# mcu.net
KiCad netlist of a schematic drawn in Altium Designer
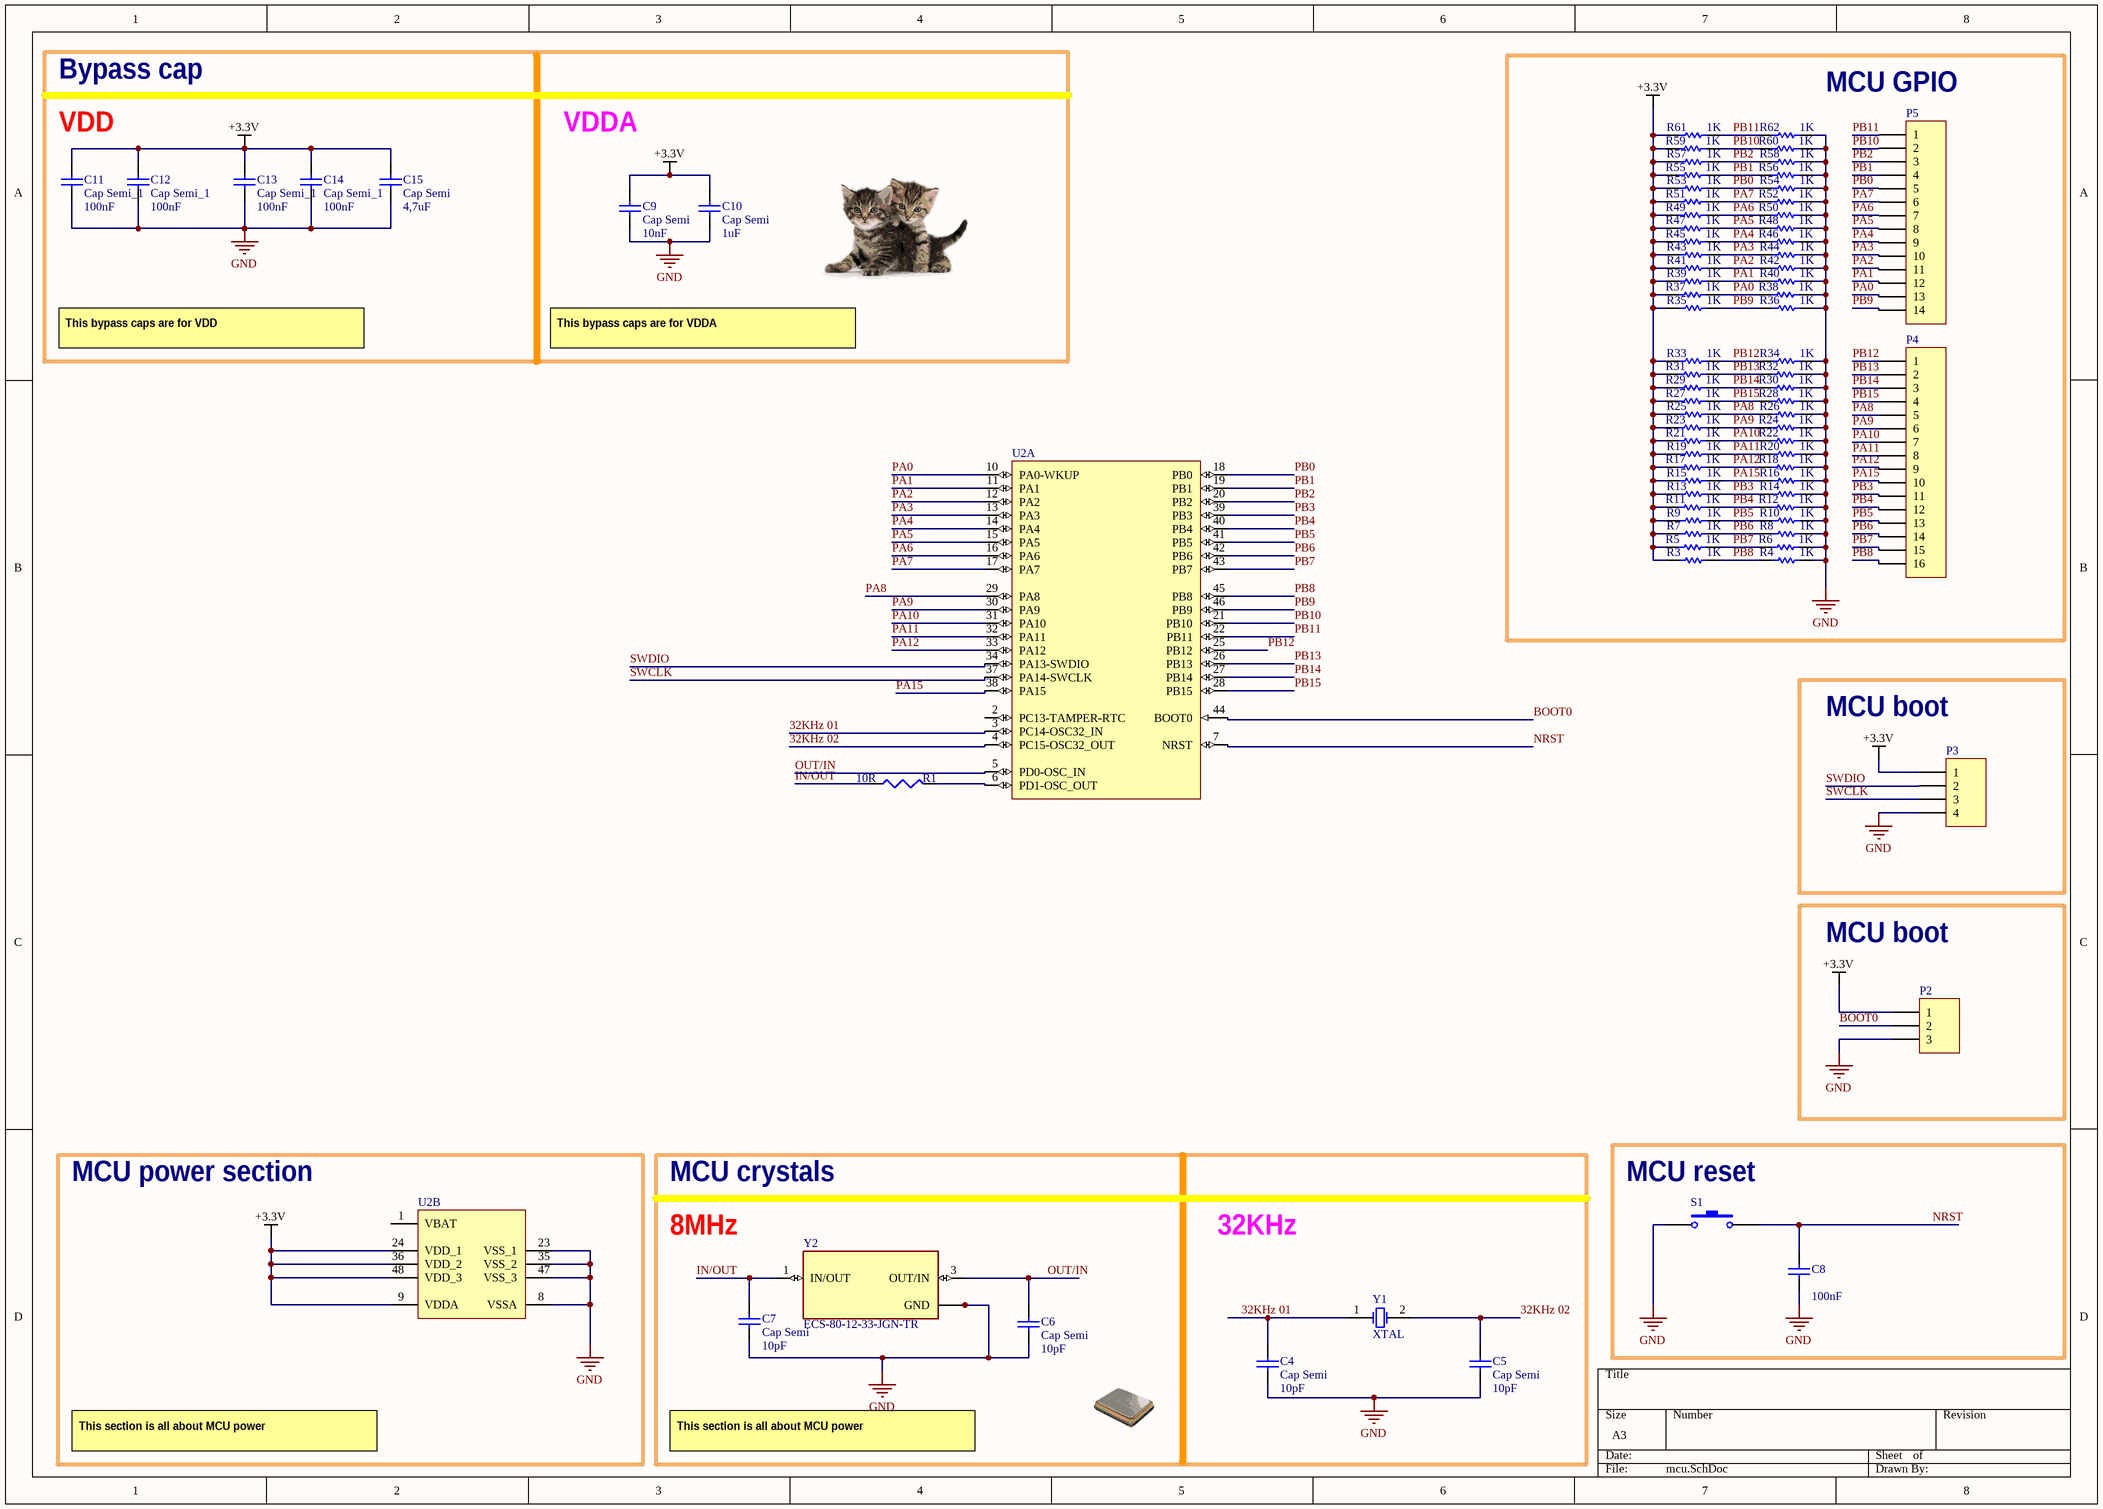
[diagram p0: mcu.SchDoc]

(export (version "E")
  (design (tool "Eeschema 10.0.6"))
  (components
    (comp (ref "C4")
      (value "Cap Semi")
      (footprint "0402")
      (description "Capacitor (Semiconductor SIM Model)")
      (fields (field (name "ALTIUM_VALUE") "10pF") (field (name "PUBLISHER") "Altium Limited"))
      (libsource (lib "Miscellaneous Devices") (part "Cap Semi"))
    )
    (comp (ref "C5")
      (value "Cap Semi")
      (footprint "0402")
      (description "Capacitor (Semiconductor SIM Model)")
      (fields (field (name "ALTIUM_VALUE") "10pF") (field (name "PUBLISHER") "Altium Limited"))
      (libsource (lib "Miscellaneous Devices") (part "Cap Semi"))
    )
    (comp (ref "C6")
      (value "Cap Semi")
      (footprint "0402")
      (description "Capacitor (Semiconductor SIM Model)")
      (fields (field (name "ALTIUM_VALUE") "10pF") (field (name "PUBLISHER") "Altium Limited"))
      (libsource (lib "Miscellaneous Devices") (part "Cap Semi"))
    )
    (comp (ref "C7")
      (value "Cap Semi")
      (footprint "0402")
      (description "Capacitor (Semiconductor SIM Model)")
      (fields (field (name "ALTIUM_VALUE") "10pF") (field (name "PUBLISHER") "Altium Limited"))
      (libsource (lib "Miscellaneous Devices") (part "Cap Semi"))
    )
    (comp (ref "C8")
      (value "100nF")
      (footprint "1608[0603]")
      (description "Capacitor (Semiconductor SIM Model)")
      (fields (field (name "PUBLISHER") "Altium Limited"))
      (libsource (lib "smartmcu") (part "Cap Semi"))
    )
    (comp (ref "C9")
      (value "Cap Semi")
      (footprint "1608[0603]")
      (description "Capacitor (Semiconductor SIM Model)")
      (fields (field (name "ALTIUM_VALUE") "10nF") (field (name "PUBLISHER") "Altium Limited"))
      (libsource (lib "Miscellaneous Devices") (part "Cap Semi"))
    )
    (comp (ref "C10")
      (value "Cap Semi")
      (footprint "1608[0603]")
      (description "Capacitor (Semiconductor SIM Model)")
      (fields (field (name "ALTIUM_VALUE") "1uF") (field (name "PUBLISHER") "Altium Limited"))
      (libsource (lib "Miscellaneous Devices") (part "Cap Semi"))
    )
    (comp (ref "C11")
      (value "Cap Semi_1")
      (footprint "1608[0603]cap")
      (description "Capacitor (Semiconductor SIM Model)")
      (fields (field (name "ALTIUM_VALUE") "100nF") (field (name "PUBLISHER") "Altium Limited"))
      (libsource (lib "smartmcu") (part "Cap Semi_1"))
    )
    (comp (ref "C12")
      (value "Cap Semi_1")
      (footprint "1608[0603]cap")
      (description "Capacitor (Semiconductor SIM Model)")
      (fields (field (name "ALTIUM_VALUE") "100nF") (field (name "PUBLISHER") "Altium Limited"))
      (libsource (lib "smartmcu") (part "Cap Semi_1"))
    )
    (comp (ref "C13")
      (value "Cap Semi_1")
      (footprint "1608[0603]cap")
      (description "Capacitor (Semiconductor SIM Model)")
      (fields (field (name "ALTIUM_VALUE") "100nF") (field (name "PUBLISHER") "Altium Limited"))
      (libsource (lib "smartmcu") (part "Cap Semi_1_2"))
    )
    (comp (ref "C14")
      (value "Cap Semi_1")
      (footprint "1608[0603]cap")
      (description "Capacitor (Semiconductor SIM Model)")
      (fields (field (name "ALTIUM_VALUE") "100nF") (field (name "PUBLISHER") "Altium Limited"))
      (libsource (lib "smartmcu") (part "Cap Semi_1_3"))
    )
    (comp (ref "C15")
      (value "Cap Semi")
      (footprint "1608[0603]cap")
      (description "Capacitor (Semiconductor SIM Model)")
      (fields (field (name "ALTIUM_VALUE") "4,7uF") (field (name "PUBLISHER") "Altium Limited"))
      (libsource (lib "smartmcu") (part "Cap Semi"))
    )
    (comp (ref "P2")
      (value "~")
      (footprint "MHDR1X3body")
      (description "Header, 3-Pin")
      (fields (field (name "PUBLISHER") "Altium Limited"))
      (libsource (lib "smartmcu") (part "MHDR1X3"))
    )
    (comp (ref "P3")
      (value "~")
      (footprint "MHDR1X4body")
      (description "Header, 4-Pin")
      (fields (field (name "PUBLISHER") "Altium Limited"))
      (libsource (lib "smartmcu") (part "MHDR1X4"))
    )
    (comp (ref "P4")
      (value "Header 16")
      (footprint "MY_FE16")
      (description "Header, 16-Pin")
      (fields (field (name "ASID PART NUMBER") "Header 16-AS"))
      (libsource (lib "Mylib+Rev+4") (part "Header 16"))
    )
    (comp (ref "P5")
      (value "Header 14")
      (footprint "MY_FE14")
      (description "Header, 14-Pin")
      (fields (field (name "ASID PART NUMBER") "Header 14-AS"))
      (libsource (lib "Mylib+Rev+4") (part "Header 14"))
    )
    (comp (ref "R1")
      (value "10R")
      (footprint "J1-0603")
      (description "Resistor")
      (fields (field (name "Comment") "Res3") (field (name "PUBLISHER") "Altium Limited"))
      (libsource (lib "Miscellaneous Devices") (part "Res3"))
    )
    (comp (ref "R3")
      (value "1K")
      (footprint "MY_0603")
      (description "Standard resistor")
      (fields (field (name "ASID PART NUMBER") "Res-AS"))
      (libsource (lib "Mylib+Rev+4") (part "Res"))
    )
    (comp (ref "R4")
      (value "1K")
      (footprint "MY_0603")
      (description "Standard resistor")
      (fields (field (name "ASID PART NUMBER") "Res-AS"))
      (libsource (lib "Mylib+Rev+4") (part "Res"))
    )
    (comp (ref "R5")
      (value "1K")
      (footprint "MY_0603")
      (description "Standard resistor")
      (fields (field (name "ASID PART NUMBER") "Res-AS"))
      (libsource (lib "Mylib+Rev+4") (part "Res"))
    )
    (comp (ref "R6")
      (value "1K")
      (footprint "MY_0603")
      (description "Standard resistor")
      (fields (field (name "ASID PART NUMBER") "Res-AS"))
      (libsource (lib "Mylib+Rev+4") (part "Res"))
    )
    (comp (ref "R7")
      (value "1K")
      (footprint "MY_0603")
      (description "Standard resistor")
      (fields (field (name "ASID PART NUMBER") "Res-AS"))
      (libsource (lib "Mylib+Rev+4") (part "Res"))
    )
    (comp (ref "R8")
      (value "1K")
      (footprint "MY_0603")
      (description "Standard resistor")
      (fields (field (name "ASID PART NUMBER") "Res-AS"))
      (libsource (lib "Mylib+Rev+4") (part "Res"))
    )
    (comp (ref "R9")
      (value "1K")
      (footprint "MY_0603")
      (description "Standard resistor")
      (fields (field (name "ASID PART NUMBER") "Res-AS"))
      (libsource (lib "Mylib+Rev+4") (part "Res"))
    )
    (comp (ref "R10")
      (value "1K")
      (footprint "MY_0603")
      (description "Standard resistor")
      (fields (field (name "ASID PART NUMBER") "Res-AS"))
      (libsource (lib "Mylib+Rev+4") (part "Res"))
    )
    (comp (ref "R11")
      (value "1K")
      (footprint "MY_0603")
      (description "Standard resistor")
      (fields (field (name "ASID PART NUMBER") "Res-AS"))
      (libsource (lib "Mylib+Rev+4") (part "Res"))
    )
    (comp (ref "R12")
      (value "1K")
      (footprint "MY_0603")
      (description "Standard resistor")
      (fields (field (name "ASID PART NUMBER") "Res-AS"))
      (libsource (lib "Mylib+Rev+4") (part "Res"))
    )
    (comp (ref "R13")
      (value "1K")
      (footprint "MY_0603")
      (description "Standard resistor")
      (fields (field (name "ASID PART NUMBER") "Res-AS"))
      (libsource (lib "Mylib+Rev+4") (part "Res"))
    )
    (comp (ref "R14")
      (value "1K")
      (footprint "MY_0603")
      (description "Standard resistor")
      (fields (field (name "ASID PART NUMBER") "Res-AS"))
      (libsource (lib "Mylib+Rev+4") (part "Res"))
    )
    (comp (ref "R15")
      (value "1K")
      (footprint "MY_0603")
      (description "Standard resistor")
      (fields (field (name "ASID PART NUMBER") "Res-AS"))
      (libsource (lib "Mylib+Rev+4") (part "Res"))
    )
    (comp (ref "R16")
      (value "1K")
      (footprint "MY_0603")
      (description "Standard resistor")
      (fields (field (name "ASID PART NUMBER") "Res-AS"))
      (libsource (lib "Mylib+Rev+4") (part "Res"))
    )
    (comp (ref "R17")
      (value "1K")
      (footprint "MY_0603")
      (description "Standard resistor")
      (fields (field (name "ASID PART NUMBER") "Res-AS"))
      (libsource (lib "Mylib+Rev+4") (part "Res"))
    )
    (comp (ref "R18")
      (value "1K")
      (footprint "MY_0603")
      (description "Standard resistor")
      (fields (field (name "ASID PART NUMBER") "Res-AS"))
      (libsource (lib "Mylib+Rev+4") (part "Res"))
    )
    (comp (ref "R19")
      (value "1K")
      (footprint "MY_0603")
      (description "Standard resistor")
      (fields (field (name "ASID PART NUMBER") "Res-AS"))
      (libsource (lib "Mylib+Rev+4") (part "Res"))
    )
    (comp (ref "R20")
      (value "1K")
      (footprint "MY_0603")
      (description "Standard resistor")
      (fields (field (name "ASID PART NUMBER") "Res-AS"))
      (libsource (lib "Mylib+Rev+4") (part "Res"))
    )
    (comp (ref "R21")
      (value "1K")
      (footprint "MY_0603")
      (description "Standard resistor")
      (fields (field (name "ASID PART NUMBER") "Res-AS"))
      (libsource (lib "Mylib+Rev+4") (part "Res"))
    )
    (comp (ref "R22")
      (value "1K")
      (footprint "MY_0603")
      (description "Standard resistor")
      (fields (field (name "ASID PART NUMBER") "Res-AS"))
      (libsource (lib "Mylib+Rev+4") (part "Res"))
    )
    (comp (ref "R23")
      (value "1K")
      (footprint "MY_0603")
      (description "Standard resistor")
      (fields (field (name "ASID PART NUMBER") "Res-AS"))
      (libsource (lib "Mylib+Rev+4") (part "Res"))
    )
    (comp (ref "R24")
      (value "1K")
      (footprint "MY_0603")
      (description "Standard resistor")
      (fields (field (name "ASID PART NUMBER") "Res-AS"))
      (libsource (lib "Mylib+Rev+4") (part "Res"))
    )
    (comp (ref "R25")
      (value "1K")
      (footprint "MY_0603")
      (description "Standard resistor")
      (fields (field (name "ASID PART NUMBER") "Res-AS"))
      (libsource (lib "Mylib+Rev+4") (part "Res"))
    )
    (comp (ref "R26")
      (value "1K")
      (footprint "MY_0603")
      (description "Standard resistor")
      (fields (field (name "ASID PART NUMBER") "Res-AS"))
      (libsource (lib "Mylib+Rev+4") (part "Res"))
    )
    (comp (ref "R27")
      (value "1K")
      (footprint "MY_0603")
      (description "Standard resistor")
      (fields (field (name "ASID PART NUMBER") "Res-AS"))
      (libsource (lib "Mylib+Rev+4") (part "Res"))
    )
    (comp (ref "R28")
      (value "1K")
      (footprint "MY_0603")
      (description "Standard resistor")
      (fields (field (name "ASID PART NUMBER") "Res-AS"))
      (libsource (lib "Mylib+Rev+4") (part "Res"))
    )
    (comp (ref "R29")
      (value "1K")
      (footprint "MY_0603")
      (description "Standard resistor")
      (fields (field (name "ASID PART NUMBER") "Res-AS"))
      (libsource (lib "Mylib+Rev+4") (part "Res"))
    )
    (comp (ref "R30")
      (value "1K")
      (footprint "MY_0603")
      (description "Standard resistor")
      (fields (field (name "ASID PART NUMBER") "Res-AS"))
      (libsource (lib "Mylib+Rev+4") (part "Res"))
    )
    (comp (ref "R31")
      (value "1K")
      (footprint "MY_0603")
      (description "Standard resistor")
      (fields (field (name "ASID PART NUMBER") "Res-AS"))
      (libsource (lib "Mylib+Rev+4") (part "Res"))
    )
    (comp (ref "R32")
      (value "1K")
      (footprint "MY_0603")
      (description "Standard resistor")
      (fields (field (name "ASID PART NUMBER") "Res-AS"))
      (libsource (lib "Mylib+Rev+4") (part "Res"))
    )
    (comp (ref "R33")
      (value "1K")
      (footprint "MY_0603")
      (description "Standard resistor")
      (fields (field (name "ASID PART NUMBER") "Res-AS"))
      (libsource (lib "Mylib+Rev+4") (part "Res"))
    )
    (comp (ref "R34")
      (value "1K")
      (footprint "MY_0603")
      (description "Standard resistor")
      (fields (field (name "ASID PART NUMBER") "Res-AS"))
      (libsource (lib "Mylib+Rev+4") (part "Res"))
    )
    (comp (ref "R35")
      (value "1K")
      (footprint "MY_0603")
      (description "Standard resistor")
      (fields (field (name "ASID PART NUMBER") "Res-AS"))
      (libsource (lib "Mylib+Rev+4") (part "Res"))
    )
    (comp (ref "R36")
      (value "1K")
      (footprint "MY_0603")
      (description "Standard resistor")
      (fields (field (name "ASID PART NUMBER") "Res-AS"))
      (libsource (lib "Mylib+Rev+4") (part "Res"))
    )
    (comp (ref "R37")
      (value "1K")
      (footprint "MY_0603")
      (description "Standard resistor")
      (fields (field (name "ASID PART NUMBER") "Res-AS"))
      (libsource (lib "Mylib+Rev+4") (part "Res"))
    )
    (comp (ref "R38")
      (value "1K")
      (footprint "MY_0603")
      (description "Standard resistor")
      (fields (field (name "ASID PART NUMBER") "Res-AS"))
      (libsource (lib "Mylib+Rev+4") (part "Res"))
    )
    (comp (ref "R39")
      (value "1K")
      (footprint "MY_0603")
      (description "Standard resistor")
      (fields (field (name "ASID PART NUMBER") "Res-AS"))
      (libsource (lib "Mylib+Rev+4") (part "Res"))
    )
    (comp (ref "R40")
      (value "1K")
      (footprint "MY_0603")
      (description "Standard resistor")
      (fields (field (name "ASID PART NUMBER") "Res-AS"))
      (libsource (lib "Mylib+Rev+4") (part "Res"))
    )
    (comp (ref "R41")
      (value "1K")
      (footprint "MY_0603")
      (description "Standard resistor")
      (fields (field (name "ASID PART NUMBER") "Res-AS"))
      (libsource (lib "Mylib+Rev+4") (part "Res"))
    )
    (comp (ref "R42")
      (value "1K")
      (footprint "MY_0603")
      (description "Standard resistor")
      (fields (field (name "ASID PART NUMBER") "Res-AS"))
      (libsource (lib "Mylib+Rev+4") (part "Res"))
    )
    (comp (ref "R43")
      (value "1K")
      (footprint "MY_0603")
      (description "Standard resistor")
      (fields (field (name "ASID PART NUMBER") "Res-AS"))
      (libsource (lib "Mylib+Rev+4") (part "Res"))
    )
    (comp (ref "R44")
      (value "1K")
      (footprint "MY_0603")
      (description "Standard resistor")
      (fields (field (name "ASID PART NUMBER") "Res-AS"))
      (libsource (lib "Mylib+Rev+4") (part "Res"))
    )
    (comp (ref "R45")
      (value "1K")
      (footprint "MY_0603")
      (description "Standard resistor")
      (fields (field (name "ASID PART NUMBER") "Res-AS"))
      (libsource (lib "Mylib+Rev+4") (part "Res"))
    )
    (comp (ref "R46")
      (value "1K")
      (footprint "MY_0603")
      (description "Standard resistor")
      (fields (field (name "ASID PART NUMBER") "Res-AS"))
      (libsource (lib "Mylib+Rev+4") (part "Res"))
    )
    (comp (ref "R47")
      (value "1K")
      (footprint "MY_0603")
      (description "Standard resistor")
      (fields (field (name "ASID PART NUMBER") "Res-AS"))
      (libsource (lib "Mylib+Rev+4") (part "Res"))
    )
    (comp (ref "R48")
      (value "1K")
      (footprint "MY_0603")
      (description "Standard resistor")
      (fields (field (name "ASID PART NUMBER") "Res-AS"))
      (libsource (lib "Mylib+Rev+4") (part "Res"))
    )
    (comp (ref "R49")
      (value "1K")
      (footprint "MY_0603")
      (description "Standard resistor")
      (fields (field (name "ASID PART NUMBER") "Res-AS"))
      (libsource (lib "Mylib+Rev+4") (part "Res"))
    )
    (comp (ref "R50")
      (value "1K")
      (footprint "MY_0603")
      (description "Standard resistor")
      (fields (field (name "ASID PART NUMBER") "Res-AS"))
      (libsource (lib "Mylib+Rev+4") (part "Res"))
    )
    (comp (ref "R51")
      (value "1K")
      (footprint "MY_0603")
      (description "Standard resistor")
      (fields (field (name "ASID PART NUMBER") "Res-AS"))
      (libsource (lib "Mylib+Rev+4") (part "Res"))
    )
    (comp (ref "R52")
      (value "1K")
      (footprint "MY_0603")
      (description "Standard resistor")
      (fields (field (name "ASID PART NUMBER") "Res-AS"))
      (libsource (lib "Mylib+Rev+4") (part "Res"))
    )
    (comp (ref "R53")
      (value "1K")
      (footprint "MY_0603")
      (description "Standard resistor")
      (fields (field (name "ASID PART NUMBER") "Res-AS"))
      (libsource (lib "Mylib+Rev+4") (part "Res"))
    )
    (comp (ref "R54")
      (value "1K")
      (footprint "MY_0603")
      (description "Standard resistor")
      (fields (field (name "ASID PART NUMBER") "Res-AS"))
      (libsource (lib "Mylib+Rev+4") (part "Res"))
    )
    (comp (ref "R55")
      (value "1K")
      (footprint "MY_0603")
      (description "Standard resistor")
      (fields (field (name "ASID PART NUMBER") "Res-AS"))
      (libsource (lib "Mylib+Rev+4") (part "Res"))
    )
    (comp (ref "R56")
      (value "1K")
      (footprint "MY_0603")
      (description "Standard resistor")
      (fields (field (name "ASID PART NUMBER") "Res-AS"))
      (libsource (lib "Mylib+Rev+4") (part "Res"))
    )
    (comp (ref "R57")
      (value "1K")
      (footprint "MY_0603")
      (description "Standard resistor")
      (fields (field (name "ASID PART NUMBER") "Res-AS"))
      (libsource (lib "Mylib+Rev+4") (part "Res"))
    )
    (comp (ref "R58")
      (value "1K")
      (footprint "MY_0603")
      (description "Standard resistor")
      (fields (field (name "ASID PART NUMBER") "Res-AS"))
      (libsource (lib "Mylib+Rev+4") (part "Res"))
    )
    (comp (ref "R59")
      (value "1K")
      (footprint "MY_0603")
      (description "Standard resistor")
      (fields (field (name "ASID PART NUMBER") "Res-AS"))
      (libsource (lib "Mylib+Rev+4") (part "Res"))
    )
    (comp (ref "R60")
      (value "1K")
      (footprint "MY_0603")
      (description "Standard resistor")
      (fields (field (name "ASID PART NUMBER") "Res-AS"))
      (libsource (lib "Mylib+Rev+4") (part "Res"))
    )
    (comp (ref "R61")
      (value "1K")
      (footprint "MY_0603")
      (description "Standard resistor")
      (fields (field (name "ASID PART NUMBER") "Res-AS"))
      (libsource (lib "Mylib+Rev+4") (part "Res"))
    )
    (comp (ref "R62")
      (value "1K")
      (footprint "MY_0603")
      (description "Standard resistor")
      (fields (field (name "ASID PART NUMBER") "Res-AS"))
      (libsource (lib "Mylib+Rev+4") (part "Res"))
    )
    (comp (ref "S1")
      (value "~")
      (footprint "SPST-2_body")
      (description "Switch")
      (fields (field (name "PUBLISHER") "Altium Limited"))
      (libsource (lib "smartmcu") (part "SW-PB"))
    )
    (comp (ref "U2")
      (value "~")
      (footprint "STM-LQFP48_N")
      (fields (field (name "PARTNUMBER") "STM32F103C8T6"))
      (libsource (lib "smartmcu") (part "STM32F103C8T6"))
    )
    (comp (ref "Y1")
      (value "XTAL")
      (footprint "R38")
      (description "Crystal Oscillator")
      (fields (field (name "PUBLISHER") "Altium Limited"))
      (libsource (lib "Miscellaneous Devices") (part "XTAL"))
    )
    (comp (ref "Y2")
      (value "ECS-80-12-33-JGN-TR")
      (footprint "XTAL_ECS-240-8-33-AGN-TR")
      (description "8MHz Â±20ppm Crystal 12pF 400 Ohms 4-SMD, No Lead")
      (fields
        (field (name "MF") "ECS Inc.")
        (field (name "BUYPART") "https://www.snapeda.com/parts/ECS-80-12-33-JGN-TR/ECS%20Inc./view-part/4477300/?ref=eda")
      )
      (libsource (lib "ECS-80-12-33-JGN-TR") (part "ECS-80-12-33-JGN-TR"))
    )
  )
  (nets
    (net (code "1") (name "+3.3V") (class "Default")
      (node (ref "C10") (pin "2") (pinfunction "2_2") (pintype "passive"))
      (node (ref "C11") (pin "2") (pinfunction "2_2") (pintype "passive"))
      (node (ref "C12") (pin "2") (pinfunction "2_2") (pintype "passive"))
      (node (ref "C13") (pin "2") (pinfunction "2_2") (pintype "passive"))
      (node (ref "C14") (pin "2") (pinfunction "2_2") (pintype "passive"))
      (node (ref "C15") (pin "2") (pinfunction "2_2") (pintype "passive"))
      (node (ref "C9") (pin "2") (pinfunction "2_2") (pintype "passive"))
      (node (ref "P2") (pin "1") (pinfunction "1_1") (pintype "passive"))
      (node (ref "P3") (pin "1") (pinfunction "1_1") (pintype "passive"))
      (node (ref "R11") (pin "1") (pinfunction "1_1") (pintype "passive"))
      (node (ref "R13") (pin "1") (pinfunction "1_1") (pintype "passive"))
      (node (ref "R15") (pin "1") (pinfunction "1_1") (pintype "passive"))
      (node (ref "R17") (pin "1") (pinfunction "1_1") (pintype "passive"))
      (node (ref "R19") (pin "1") (pinfunction "1_1") (pintype "passive"))
      (node (ref "R21") (pin "1") (pinfunction "1_1") (pintype "passive"))
      (node (ref "R23") (pin "1") (pinfunction "1_1") (pintype "passive"))
      (node (ref "R25") (pin "1") (pinfunction "1_1") (pintype "passive"))
      (node (ref "R27") (pin "1") (pinfunction "1_1") (pintype "passive"))
      (node (ref "R29") (pin "1") (pinfunction "1_1") (pintype "passive"))
      (node (ref "R3") (pin "1") (pinfunction "1_1") (pintype "passive"))
      (node (ref "R31") (pin "1") (pinfunction "1_1") (pintype "passive"))
      (node (ref "R33") (pin "1") (pinfunction "1_1") (pintype "passive"))
      (node (ref "R35") (pin "1") (pinfunction "1_1") (pintype "passive"))
      (node (ref "R37") (pin "1") (pinfunction "1_1") (pintype "passive"))
      (node (ref "R39") (pin "1") (pinfunction "1_1") (pintype "passive"))
      (node (ref "R41") (pin "1") (pinfunction "1_1") (pintype "passive"))
      (node (ref "R43") (pin "1") (pinfunction "1_1") (pintype "passive"))
      (node (ref "R45") (pin "1") (pinfunction "1_1") (pintype "passive"))
      (node (ref "R47") (pin "1") (pinfunction "1_1") (pintype "passive"))
      (node (ref "R49") (pin "1") (pinfunction "1_1") (pintype "passive"))
      (node (ref "R5") (pin "1") (pinfunction "1_1") (pintype "passive"))
      (node (ref "R51") (pin "1") (pinfunction "1_1") (pintype "passive"))
      (node (ref "R53") (pin "1") (pinfunction "1_1") (pintype "passive"))
      (node (ref "R55") (pin "1") (pinfunction "1_1") (pintype "passive"))
      (node (ref "R57") (pin "1") (pinfunction "1_1") (pintype "passive"))
      (node (ref "R59") (pin "1") (pinfunction "1_1") (pintype "passive"))
      (node (ref "R61") (pin "1") (pinfunction "1_1") (pintype "passive"))
      (node (ref "R7") (pin "1") (pinfunction "1_1") (pintype "passive"))
      (node (ref "R9") (pin "1") (pinfunction "1_1") (pintype "passive"))
      (node (ref "U2") (pin "24") (pinfunction "VDD_1_24") (pintype "power_in"))
      (node (ref "U2") (pin "36") (pinfunction "VDD_2_36") (pintype "power_in"))
      (node (ref "U2") (pin "48") (pinfunction "VDD_3_48") (pintype "power_in"))
      (node (ref "U2") (pin "9") (pinfunction "VDDA_9") (pintype "power_in"))
    )
    (net (code "2") (name "/32KHz 01") (class "Default")
      (node (ref "C4") (pin "2") (pinfunction "2_2") (pintype "passive"))
      (node (ref "U2") (pin "3") (pinfunction "PC14-OSC32_IN_3") (pintype "bidirectional"))
      (node (ref "Y1") (pin "1") (pinfunction "OSC1_1") (pintype "passive"))
    )
    (net (code "3") (name "/32KHz 02") (class "Default")
      (node (ref "C5") (pin "2") (pinfunction "2_2") (pintype "passive"))
      (node (ref "U2") (pin "4") (pinfunction "PC15-OSC32_OUT_4") (pintype "bidirectional"))
      (node (ref "Y1") (pin "2") (pinfunction "OSC2_2") (pintype "passive"))
    )
    (net (code "4") (name "/BOOT0") (class "Default")
      (node (ref "P2") (pin "2") (pinfunction "2_2") (pintype "passive"))
      (node (ref "U2") (pin "44") (pinfunction "BOOT0_44") (pintype "input"))
    )
    (net (code "5") (name "/IN{slash}OUT") (class "Default")
      (node (ref "C7") (pin "2") (pinfunction "2_2") (pintype "passive"))
      (node (ref "R1") (pin "1") (pinfunction "1_1") (pintype "passive"))
      (node (ref "Y2") (pin "1") (pinfunction "IN/OUT_1") (pintype "bidirectional"))
    )
    (net (code "6") (name "/NRST") (class "Default")
      (node (ref "C8") (pin "2") (pinfunction "2_2") (pintype "passive"))
      (node (ref "S1") (pin "2") (pinfunction "2_2") (pintype "passive"))
      (node (ref "U2") (pin "7") (pinfunction "NRST_7") (pintype "bidirectional"))
    )
    (net (code "7") (name "/OUT{slash}IN") (class "Default")
      (node (ref "C6") (pin "2") (pinfunction "2_2") (pintype "passive"))
      (node (ref "U2") (pin "5") (pinfunction "PD0-OSC_IN_5") (pintype "bidirectional"))
      (node (ref "Y2") (pin "3") (pinfunction "OUT/IN_3") (pintype "bidirectional"))
    )
    (net (code "8") (name "/PA0") (class "Default")
      (node (ref "P5") (pin "13") (pinfunction "13_13") (pintype "passive"))
      (node (ref "R37") (pin "2") (pinfunction "2_2") (pintype "passive"))
      (node (ref "R38") (pin "1") (pinfunction "1_1") (pintype "passive"))
      (node (ref "U2") (pin "10") (pinfunction "PA0-WKUP_10") (pintype "bidirectional"))
    )
    (net (code "9") (name "/PA1") (class "Default")
      (node (ref "P5") (pin "12") (pinfunction "12_12") (pintype "passive"))
      (node (ref "R39") (pin "2") (pinfunction "2_2") (pintype "passive"))
      (node (ref "R40") (pin "1") (pinfunction "1_1") (pintype "passive"))
      (node (ref "U2") (pin "11") (pinfunction "PA1_11") (pintype "bidirectional"))
    )
    (net (code "10") (name "/PA2") (class "Default")
      (node (ref "P5") (pin "11") (pinfunction "11_11") (pintype "passive"))
      (node (ref "R41") (pin "2") (pinfunction "2_2") (pintype "passive"))
      (node (ref "R42") (pin "1") (pinfunction "1_1") (pintype "passive"))
      (node (ref "U2") (pin "12") (pinfunction "PA2_12") (pintype "bidirectional"))
    )
    (net (code "11") (name "/PA3") (class "Default")
      (node (ref "P5") (pin "10") (pinfunction "10_10") (pintype "passive"))
      (node (ref "R43") (pin "2") (pinfunction "2_2") (pintype "passive"))
      (node (ref "R44") (pin "1") (pinfunction "1_1") (pintype "passive"))
      (node (ref "U2") (pin "13") (pinfunction "PA3_13") (pintype "bidirectional"))
    )
    (net (code "12") (name "/PA4") (class "Default")
      (node (ref "P5") (pin "9") (pinfunction "9_9") (pintype "passive"))
      (node (ref "R45") (pin "2") (pinfunction "2_2") (pintype "passive"))
      (node (ref "R46") (pin "1") (pinfunction "1_1") (pintype "passive"))
      (node (ref "U2") (pin "14") (pinfunction "PA4_14") (pintype "bidirectional"))
    )
    (net (code "13") (name "/PA5") (class "Default")
      (node (ref "P5") (pin "8") (pinfunction "8_8") (pintype "passive"))
      (node (ref "R47") (pin "2") (pinfunction "2_2") (pintype "passive"))
      (node (ref "R48") (pin "1") (pinfunction "1_1") (pintype "passive"))
      (node (ref "U2") (pin "15") (pinfunction "PA5_15") (pintype "bidirectional"))
    )
    (net (code "14") (name "/PA6") (class "Default")
      (node (ref "P5") (pin "7") (pinfunction "7_7") (pintype "passive"))
      (node (ref "R49") (pin "2") (pinfunction "2_2") (pintype "passive"))
      (node (ref "R50") (pin "1") (pinfunction "1_1") (pintype "passive"))
      (node (ref "U2") (pin "16") (pinfunction "PA6_16") (pintype "bidirectional"))
    )
    (net (code "15") (name "/PA7") (class "Default")
      (node (ref "P5") (pin "6") (pinfunction "6_6") (pintype "passive"))
      (node (ref "R51") (pin "2") (pinfunction "2_2") (pintype "passive"))
      (node (ref "R52") (pin "1") (pinfunction "1_1") (pintype "passive"))
      (node (ref "U2") (pin "17") (pinfunction "PA7_17") (pintype "bidirectional"))
    )
    (net (code "16") (name "/PA8") (class "Default")
      (node (ref "P4") (pin "5") (pinfunction "5_5") (pintype "passive"))
      (node (ref "R25") (pin "2") (pinfunction "2_2") (pintype "passive"))
      (node (ref "R26") (pin "1") (pinfunction "1_1") (pintype "passive"))
      (node (ref "U2") (pin "29") (pinfunction "PA8_29") (pintype "bidirectional"))
    )
    (net (code "17") (name "/PA9") (class "Default")
      (node (ref "P4") (pin "6") (pinfunction "6_6") (pintype "passive"))
      (node (ref "R23") (pin "2") (pinfunction "2_2") (pintype "passive"))
      (node (ref "R24") (pin "1") (pinfunction "1_1") (pintype "passive"))
      (node (ref "U2") (pin "30") (pinfunction "PA9_30") (pintype "bidirectional"))
    )
    (net (code "18") (name "/PA10") (class "Default")
      (node (ref "P4") (pin "7") (pinfunction "7_7") (pintype "passive"))
      (node (ref "R21") (pin "2") (pinfunction "2_2") (pintype "passive"))
      (node (ref "R22") (pin "1") (pinfunction "1_1") (pintype "passive"))
      (node (ref "U2") (pin "31") (pinfunction "PA10_31") (pintype "bidirectional"))
    )
    (net (code "19") (name "/PA11") (class "Default")
      (node (ref "P4") (pin "8") (pinfunction "8_8") (pintype "passive"))
      (node (ref "R19") (pin "2") (pinfunction "2_2") (pintype "passive"))
      (node (ref "R20") (pin "1") (pinfunction "1_1") (pintype "passive"))
      (node (ref "U2") (pin "32") (pinfunction "PA11_32") (pintype "bidirectional"))
    )
    (net (code "20") (name "/PA12") (class "Default")
      (node (ref "P4") (pin "9") (pinfunction "9_9") (pintype "passive"))
      (node (ref "R17") (pin "2") (pinfunction "2_2") (pintype "passive"))
      (node (ref "R18") (pin "1") (pinfunction "1_1") (pintype "passive"))
      (node (ref "U2") (pin "33") (pinfunction "PA12_33") (pintype "bidirectional"))
    )
    (net (code "21") (name "/PA15") (class "Default")
      (node (ref "P4") (pin "10") (pinfunction "10_10") (pintype "passive"))
      (node (ref "R15") (pin "2") (pinfunction "2_2") (pintype "passive"))
      (node (ref "R16") (pin "1") (pinfunction "1_1") (pintype "passive"))
      (node (ref "U2") (pin "38") (pinfunction "PA15_38") (pintype "bidirectional"))
    )
    (net (code "22") (name "/PB0") (class "Default")
      (node (ref "P5") (pin "5") (pinfunction "5_5") (pintype "passive"))
      (node (ref "R53") (pin "2") (pinfunction "2_2") (pintype "passive"))
      (node (ref "R54") (pin "1") (pinfunction "1_1") (pintype "passive"))
      (node (ref "U2") (pin "18") (pinfunction "PB0_18") (pintype "bidirectional"))
    )
    (net (code "23") (name "/PB1") (class "Default")
      (node (ref "P5") (pin "4") (pinfunction "4_4") (pintype "passive"))
      (node (ref "R55") (pin "2") (pinfunction "2_2") (pintype "passive"))
      (node (ref "R56") (pin "1") (pinfunction "1_1") (pintype "passive"))
      (node (ref "U2") (pin "19") (pinfunction "PB1_19") (pintype "bidirectional"))
    )
    (net (code "24") (name "/PB2") (class "Default")
      (node (ref "P5") (pin "3") (pinfunction "3_3") (pintype "passive"))
      (node (ref "R57") (pin "2") (pinfunction "2_2") (pintype "passive"))
      (node (ref "R58") (pin "1") (pinfunction "1_1") (pintype "passive"))
      (node (ref "U2") (pin "20") (pinfunction "PB2_20") (pintype "bidirectional"))
    )
    (net (code "25") (name "/PB3") (class "Default")
      (node (ref "P4") (pin "11") (pinfunction "11_11") (pintype "passive"))
      (node (ref "R13") (pin "2") (pinfunction "2_2") (pintype "passive"))
      (node (ref "R14") (pin "1") (pinfunction "1_1") (pintype "passive"))
      (node (ref "U2") (pin "39") (pinfunction "PB3_39") (pintype "bidirectional"))
    )
    (net (code "26") (name "/PB4") (class "Default")
      (node (ref "P4") (pin "12") (pinfunction "12_12") (pintype "passive"))
      (node (ref "R11") (pin "2") (pinfunction "2_2") (pintype "passive"))
      (node (ref "R12") (pin "1") (pinfunction "1_1") (pintype "passive"))
      (node (ref "U2") (pin "40") (pinfunction "PB4_40") (pintype "bidirectional"))
    )
    (net (code "27") (name "/PB5") (class "Default")
      (node (ref "P4") (pin "13") (pinfunction "13_13") (pintype "passive"))
      (node (ref "R10") (pin "1") (pinfunction "1_1") (pintype "passive"))
      (node (ref "R9") (pin "2") (pinfunction "2_2") (pintype "passive"))
      (node (ref "U2") (pin "41") (pinfunction "PB5_41") (pintype "bidirectional"))
    )
    (net (code "28") (name "/PB6") (class "Default")
      (node (ref "P4") (pin "14") (pinfunction "14_14") (pintype "passive"))
      (node (ref "R7") (pin "2") (pinfunction "2_2") (pintype "passive"))
      (node (ref "R8") (pin "1") (pinfunction "1_1") (pintype "passive"))
      (node (ref "U2") (pin "42") (pinfunction "PB6_42") (pintype "bidirectional"))
    )
    (net (code "29") (name "/PB7") (class "Default")
      (node (ref "P4") (pin "15") (pinfunction "15_15") (pintype "passive"))
      (node (ref "R5") (pin "2") (pinfunction "2_2") (pintype "passive"))
      (node (ref "R6") (pin "1") (pinfunction "1_1") (pintype "passive"))
      (node (ref "U2") (pin "43") (pinfunction "PB7_43") (pintype "bidirectional"))
    )
    (net (code "30") (name "/PB8") (class "Default")
      (node (ref "P4") (pin "16") (pinfunction "16_16") (pintype "passive"))
      (node (ref "R3") (pin "2") (pinfunction "2_2") (pintype "passive"))
      (node (ref "R4") (pin "1") (pinfunction "1_1") (pintype "passive"))
      (node (ref "U2") (pin "45") (pinfunction "PB8_45") (pintype "bidirectional"))
    )
    (net (code "31") (name "/PB9") (class "Default")
      (node (ref "P5") (pin "14") (pinfunction "14_14") (pintype "passive"))
      (node (ref "R35") (pin "2") (pinfunction "2_2") (pintype "passive"))
      (node (ref "R36") (pin "1") (pinfunction "1_1") (pintype "passive"))
      (node (ref "U2") (pin "46") (pinfunction "PB9_46") (pintype "bidirectional"))
    )
    (net (code "32") (name "/PB10") (class "Default")
      (node (ref "P5") (pin "2") (pinfunction "2_2") (pintype "passive"))
      (node (ref "R59") (pin "2") (pinfunction "2_2") (pintype "passive"))
      (node (ref "R60") (pin "1") (pinfunction "1_1") (pintype "passive"))
      (node (ref "U2") (pin "21") (pinfunction "PB10_21") (pintype "bidirectional"))
    )
    (net (code "33") (name "/PB11") (class "Default")
      (node (ref "P5") (pin "1") (pinfunction "1_1") (pintype "passive"))
      (node (ref "R61") (pin "2") (pinfunction "2_2") (pintype "passive"))
      (node (ref "R62") (pin "1") (pinfunction "1_1") (pintype "passive"))
      (node (ref "U2") (pin "22") (pinfunction "PB11_22") (pintype "bidirectional"))
    )
    (net (code "34") (name "/PB12") (class "Default")
      (node (ref "P4") (pin "1") (pinfunction "1_1") (pintype "passive"))
      (node (ref "R33") (pin "2") (pinfunction "2_2") (pintype "passive"))
      (node (ref "R34") (pin "1") (pinfunction "1_1") (pintype "passive"))
      (node (ref "U2") (pin "25") (pinfunction "PB12_25") (pintype "bidirectional"))
    )
    (net (code "35") (name "/PB13") (class "Default")
      (node (ref "P4") (pin "2") (pinfunction "2_2") (pintype "passive"))
      (node (ref "R31") (pin "2") (pinfunction "2_2") (pintype "passive"))
      (node (ref "R32") (pin "1") (pinfunction "1_1") (pintype "passive"))
      (node (ref "U2") (pin "26") (pinfunction "PB13_26") (pintype "bidirectional"))
    )
    (net (code "36") (name "/PB14") (class "Default")
      (node (ref "P4") (pin "3") (pinfunction "3_3") (pintype "passive"))
      (node (ref "R29") (pin "2") (pinfunction "2_2") (pintype "passive"))
      (node (ref "R30") (pin "1") (pinfunction "1_1") (pintype "passive"))
      (node (ref "U2") (pin "27") (pinfunction "PB14_27") (pintype "bidirectional"))
    )
    (net (code "37") (name "/PB15") (class "Default")
      (node (ref "P4") (pin "4") (pinfunction "4_4") (pintype "passive"))
      (node (ref "R27") (pin "2") (pinfunction "2_2") (pintype "passive"))
      (node (ref "R28") (pin "1") (pinfunction "1_1") (pintype "passive"))
      (node (ref "U2") (pin "28") (pinfunction "PB15_28") (pintype "bidirectional"))
    )
    (net (code "38") (name "/SWCLK") (class "Default")
      (node (ref "P3") (pin "3") (pinfunction "3_3") (pintype "passive"))
      (node (ref "U2") (pin "37") (pinfunction "PA14-SWCLK_37") (pintype "bidirectional"))
    )
    (net (code "39") (name "/SWDIO") (class "Default")
      (node (ref "P3") (pin "2") (pinfunction "2_2") (pintype "passive"))
      (node (ref "U2") (pin "34") (pinfunction "PA13-SWDIO_34") (pintype "bidirectional"))
    )
    (net (code "40") (name "GND") (class "Default")
      (node (ref "C10") (pin "1") (pinfunction "1_1") (pintype "passive"))
      (node (ref "C11") (pin "1") (pinfunction "1_1") (pintype "passive"))
      (node (ref "C12") (pin "1") (pinfunction "1_1") (pintype "passive"))
      (node (ref "C13") (pin "1") (pinfunction "1_1") (pintype "passive"))
      (node (ref "C14") (pin "1") (pinfunction "1_1") (pintype "passive"))
      (node (ref "C15") (pin "1") (pinfunction "1_1") (pintype "passive"))
      (node (ref "C4") (pin "1") (pinfunction "1_1") (pintype "passive"))
      (node (ref "C5") (pin "1") (pinfunction "1_1") (pintype "passive"))
      (node (ref "C6") (pin "1") (pinfunction "1_1") (pintype "passive"))
      (node (ref "C7") (pin "1") (pinfunction "1_1") (pintype "passive"))
      (node (ref "C8") (pin "1") (pinfunction "1_1") (pintype "passive"))
      (node (ref "C9") (pin "1") (pinfunction "1_1") (pintype "passive"))
      (node (ref "P2") (pin "3") (pinfunction "3_3") (pintype "passive"))
      (node (ref "P3") (pin "4") (pinfunction "4_4") (pintype "passive"))
      (node (ref "R10") (pin "2") (pinfunction "2_2") (pintype "passive"))
      (node (ref "R12") (pin "2") (pinfunction "2_2") (pintype "passive"))
      (node (ref "R14") (pin "2") (pinfunction "2_2") (pintype "passive"))
      (node (ref "R16") (pin "2") (pinfunction "2_2") (pintype "passive"))
      (node (ref "R18") (pin "2") (pinfunction "2_2") (pintype "passive"))
      (node (ref "R20") (pin "2") (pinfunction "2_2") (pintype "passive"))
      (node (ref "R22") (pin "2") (pinfunction "2_2") (pintype "passive"))
      (node (ref "R24") (pin "2") (pinfunction "2_2") (pintype "passive"))
      (node (ref "R26") (pin "2") (pinfunction "2_2") (pintype "passive"))
      (node (ref "R28") (pin "2") (pinfunction "2_2") (pintype "passive"))
      (node (ref "R30") (pin "2") (pinfunction "2_2") (pintype "passive"))
      (node (ref "R32") (pin "2") (pinfunction "2_2") (pintype "passive"))
      (node (ref "R34") (pin "2") (pinfunction "2_2") (pintype "passive"))
      (node (ref "R36") (pin "2") (pinfunction "2_2") (pintype "passive"))
      (node (ref "R38") (pin "2") (pinfunction "2_2") (pintype "passive"))
      (node (ref "R4") (pin "2") (pinfunction "2_2") (pintype "passive"))
      (node (ref "R40") (pin "2") (pinfunction "2_2") (pintype "passive"))
      (node (ref "R42") (pin "2") (pinfunction "2_2") (pintype "passive"))
      (node (ref "R44") (pin "2") (pinfunction "2_2") (pintype "passive"))
      (node (ref "R46") (pin "2") (pinfunction "2_2") (pintype "passive"))
      (node (ref "R48") (pin "2") (pinfunction "2_2") (pintype "passive"))
      (node (ref "R50") (pin "2") (pinfunction "2_2") (pintype "passive"))
      (node (ref "R52") (pin "2") (pinfunction "2_2") (pintype "passive"))
      (node (ref "R54") (pin "2") (pinfunction "2_2") (pintype "passive"))
      (node (ref "R56") (pin "2") (pinfunction "2_2") (pintype "passive"))
      (node (ref "R58") (pin "2") (pinfunction "2_2") (pintype "passive"))
      (node (ref "R6") (pin "2") (pinfunction "2_2") (pintype "passive"))
      (node (ref "R60") (pin "2") (pinfunction "2_2") (pintype "passive"))
      (node (ref "R62") (pin "2") (pinfunction "2_2") (pintype "passive"))
      (node (ref "R8") (pin "2") (pinfunction "2_2") (pintype "passive"))
      (node (ref "S1") (pin "1") (pinfunction "1_1") (pintype "passive"))
      (node (ref "U2") (pin "23") (pinfunction "VSS_1_23") (pintype "power_in"))
      (node (ref "U2") (pin "35") (pinfunction "VSS_2_35") (pintype "power_in"))
      (node (ref "U2") (pin "47") (pinfunction "VSS_3_47") (pintype "power_in"))
      (node (ref "U2") (pin "8") (pinfunction "VSSA_8") (pintype "power_in"))
      (node (ref "Y2") (pin "2") (pinfunction "GND_2") (pintype "power_in"))
      (node (ref "Y2") (pin "4") (pinfunction "GND_4") (pintype "power_in"))
    )
    (net (code "41") (name "Net-(U2A-PD1-OSC_OUT)") (class "Default")
      (node (ref "R1") (pin "2") (pinfunction "2_2") (pintype "passive"))
      (node (ref "U2") (pin "6") (pinfunction "PD1-OSC_OUT_6") (pintype "bidirectional"))
    )
    (net (code "42") (name "unconnected-(U2A-PC13-TAMPER-RTC-Pad2)") (class "Default")
      (node (ref "U2") (pin "2") (pinfunction "PC13-TAMPER-RTC_2") (pintype "bidirectional"))
    )
    (net (code "43") (name "unconnected-(U2B-VBAT-Pad1)") (class "Default")
      (node (ref "U2") (pin "1") (pinfunction "VBAT_1") (pintype "power_in"))
    )
  )
)
